# GCDuino5v_v2.net
KiCad netlist of a schematic drawn in EAGLE
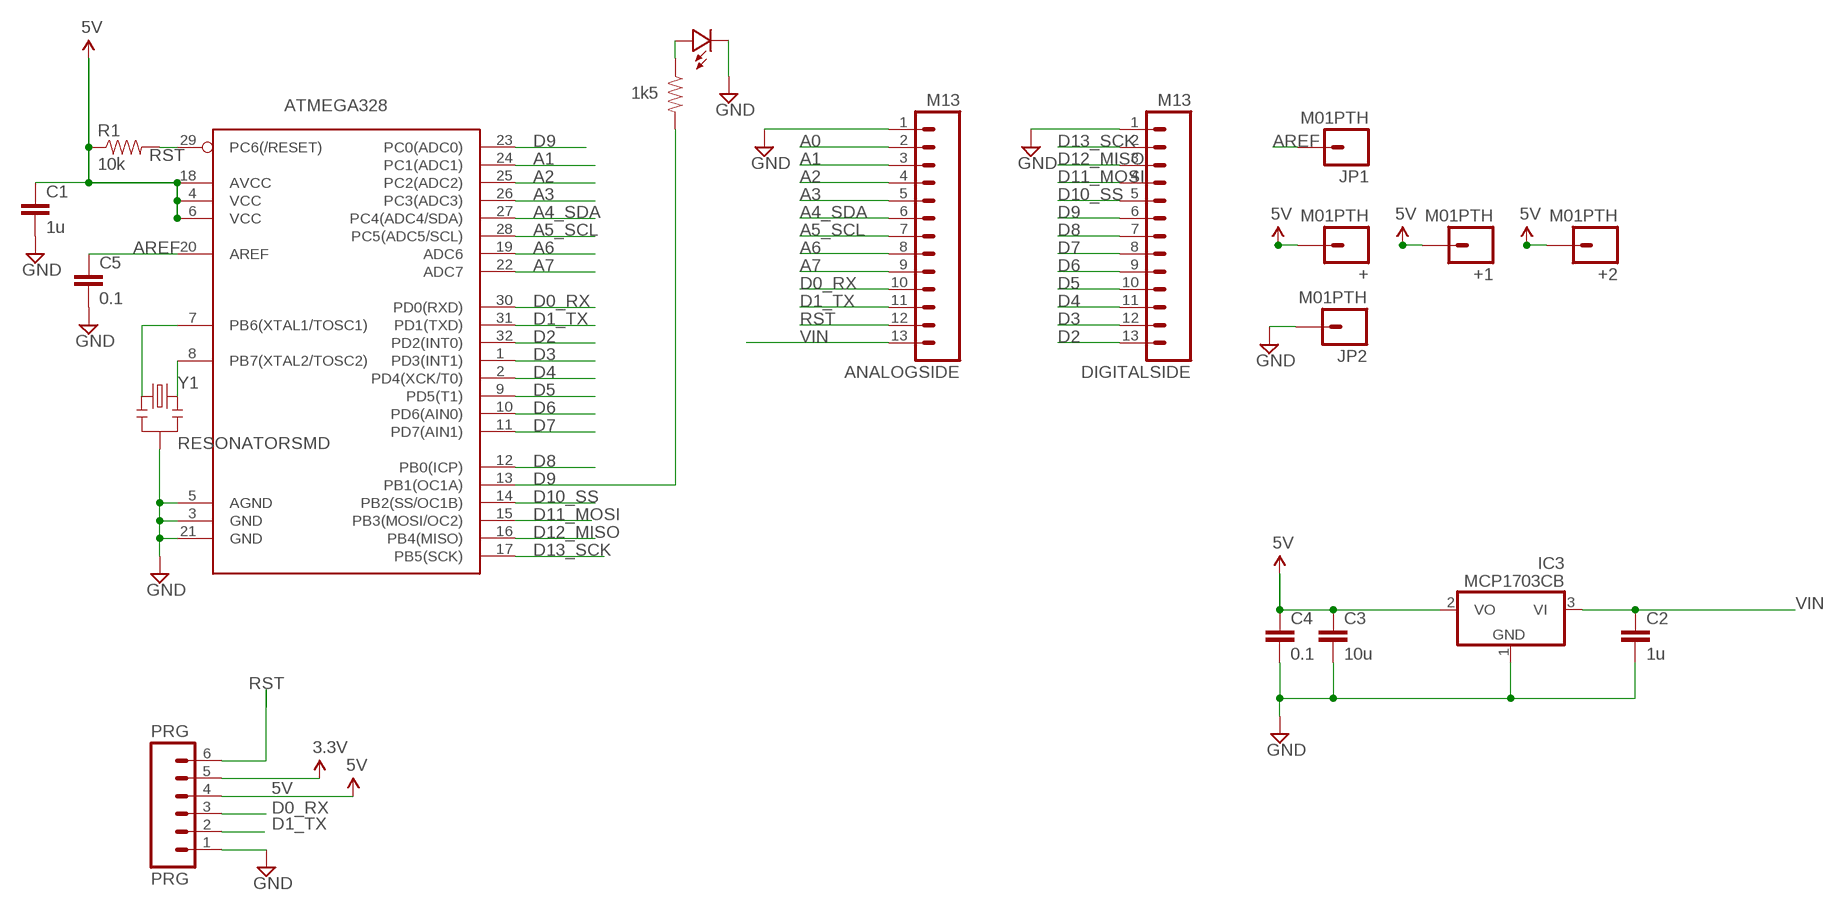
[diagram p0: schematic, sheet 1]

(export (version "E")
  (design (tool "Eeschema 10.0.6"))
  (components
    (comp (ref "+")
      (value "M01PTH")
      (footprint "eagle-import:1X01")
      (libsource (lib "eagle-import") (part "M01PTH"))
    )
    (comp (ref "+1")
      (value "M01PTH")
      (footprint "eagle-import:1X01")
      (libsource (lib "eagle-import") (part "M01PTH"))
    )
    (comp (ref "+2")
      (value "M01PTH")
      (footprint "eagle-import:1X01")
      (libsource (lib "eagle-import") (part "M01PTH"))
    )
    (comp (ref "ANALOGSIDE")
      (value "M13")
      (footprint "eagle-import:1X13")
      (libsource (lib "eagle-import") (part "M13"))
    )
    (comp (ref "ATMEGA328")
      (value "ATMega-328")
      (footprint "eagle-import:TQFP32-08")
      (libsource (lib "eagle-import") (part "ATMEGA168/328TQFP32"))
    )
    (comp (ref "C1")
      (value "1u")
      (footprint "eagle-import:0805")
      (libsource (lib "eagle-import") (part "CAP0805"))
    )
    (comp (ref "C2")
      (value "1u")
      (footprint "eagle-import:0805")
      (libsource (lib "eagle-import") (part "CAP0805"))
    )
    (comp (ref "C3")
      (value "10u")
      (footprint "eagle-import:0805-CAP")
      (libsource (lib "eagle-import") (part "CAP0805-CAP"))
    )
    (comp (ref "C4")
      (value "0.1")
      (footprint "eagle-import:0805")
      (libsource (lib "eagle-import") (part "CAP0805"))
    )
    (comp (ref "C5")
      (value "0.1")
      (footprint "eagle-import:0805")
      (libsource (lib "eagle-import") (part "CAP0805"))
    )
    (comp (ref "DIGITALSIDE")
      (value "M13")
      (footprint "eagle-import:1X13")
      (libsource (lib "eagle-import") (part "M13"))
    )
    (comp (ref "IC3")
      (value "MCP1703CB")
      (footprint "eagle-import:SOT23")
      (libsource (lib "eagle-import") (part "MCP1703CB"))
    )
    (comp (ref "JP1")
      (value "M01PTH")
      (footprint "eagle-import:1X01")
      (libsource (lib "eagle-import") (part "M01PTH"))
    )
    (comp (ref "JP2")
      (value "M01PTH")
      (footprint "eagle-import:1X01")
      (libsource (lib "eagle-import") (part "M01PTH"))
    )
    (comp (ref "PRG")
      (value "PRG")
      (footprint "eagle-import:1X06")
      (libsource (lib "eagle-import") (part "M06SIP"))
    )
    (comp (ref "R1")
      (value "10k")
      (footprint "eagle-import:0805")
      (libsource (lib "eagle-import") (part "RESISTOR0805"))
    )
    (comp (ref "R2")
      (value "1k5")
      (footprint "eagle-import:0805")
      (libsource (lib "eagle-import") (part "RESISTOR0805"))
    )
    (comp (ref "U$2")
      (value "LED0805")
      (footprint "eagle-import:0805-LED")
      (libsource (lib "eagle-import") (part "LED0805"))
    )
    (comp (ref "Y1")
      (value "RESONATORSMD")
      (footprint "eagle-import:RESONATOR-SMD")
      (libsource (lib "eagle-import") (part "RESONATORSMD"))
    )
  )
  (nets
    (net (code "1") (name "/A0") (class "Default")
      (node (ref "ANALOGSIDE") (pin "2") (pinfunction "2_2") (pintype "passive"))
      (node (ref "ATMEGA328") (pin "23") (pinfunction "PC0(ADC0)_23") (pintype "bidirectional"))
    )
    (net (code "2") (name "/A1") (class "Default")
      (node (ref "ANALOGSIDE") (pin "3") (pinfunction "3_3") (pintype "passive"))
      (node (ref "ATMEGA328") (pin "24") (pinfunction "PC1(ADC1)_24") (pintype "bidirectional"))
    )
    (net (code "3") (name "/A2") (class "Default")
      (node (ref "ANALOGSIDE") (pin "4") (pinfunction "4_4") (pintype "passive"))
      (node (ref "ATMEGA328") (pin "25") (pinfunction "PC2(ADC2)_25") (pintype "bidirectional"))
    )
    (net (code "4") (name "/A3") (class "Default")
      (node (ref "ANALOGSIDE") (pin "5") (pinfunction "5_5") (pintype "passive"))
      (node (ref "ATMEGA328") (pin "26") (pinfunction "PC3(ADC3)_26") (pintype "bidirectional"))
    )
    (net (code "5") (name "/A4_SDA") (class "Default")
      (node (ref "ANALOGSIDE") (pin "6") (pinfunction "6_6") (pintype "passive"))
      (node (ref "ATMEGA328") (pin "27") (pinfunction "PC4(ADC4/SDA)_27") (pintype "bidirectional"))
    )
    (net (code "6") (name "/A5_SCL") (class "Default")
      (node (ref "ANALOGSIDE") (pin "7") (pinfunction "7_7") (pintype "passive"))
      (node (ref "ATMEGA328") (pin "28") (pinfunction "PC5(ADC5/SCL)_28") (pintype "bidirectional"))
    )
    (net (code "7") (name "/A6") (class "Default")
      (node (ref "ANALOGSIDE") (pin "8") (pinfunction "8_8") (pintype "passive"))
      (node (ref "ATMEGA328") (pin "19") (pinfunction "ADC6_19") (pintype "bidirectional"))
    )
    (net (code "8") (name "/A7") (class "Default")
      (node (ref "ANALOGSIDE") (pin "9") (pinfunction "9_9") (pintype "passive"))
      (node (ref "ATMEGA328") (pin "22") (pinfunction "ADC7_22") (pintype "bidirectional"))
    )
    (net (code "9") (name "/AREF") (class "Default")
      (node (ref "ATMEGA328") (pin "20") (pinfunction "AREF_20") (pintype "bidirectional"))
      (node (ref "C5") (pin "1") (pinfunction "1_1") (pintype "passive"))
      (node (ref "JP1") (pin "1") (pinfunction "1_1") (pintype "passive"))
    )
    (net (code "10") (name "/D0_RX") (class "Default")
      (node (ref "ANALOGSIDE") (pin "10") (pinfunction "10_10") (pintype "passive"))
      (node (ref "ATMEGA328") (pin "30") (pinfunction "PD0(RXD)_30") (pintype "bidirectional"))
      (node (ref "PRG") (pin "3") (pinfunction "3_3") (pintype "passive"))
    )
    (net (code "11") (name "/D1_TX") (class "Default")
      (node (ref "ANALOGSIDE") (pin "11") (pinfunction "11_11") (pintype "passive"))
      (node (ref "ATMEGA328") (pin "31") (pinfunction "PD1(TXD)_31") (pintype "bidirectional"))
      (node (ref "PRG") (pin "2") (pinfunction "2_2") (pintype "passive"))
    )
    (net (code "12") (name "/D2") (class "Default")
      (node (ref "ATMEGA328") (pin "32") (pinfunction "PD2(INT0)_32") (pintype "bidirectional"))
      (node (ref "DIGITALSIDE") (pin "13") (pinfunction "13_13") (pintype "passive"))
    )
    (net (code "13") (name "/D3") (class "Default")
      (node (ref "ATMEGA328") (pin "1") (pinfunction "PD3(INT1)_1") (pintype "bidirectional"))
      (node (ref "DIGITALSIDE") (pin "12") (pinfunction "12_12") (pintype "passive"))
    )
    (net (code "14") (name "/D4") (class "Default")
      (node (ref "ATMEGA328") (pin "2") (pinfunction "PD4(XCK/T0)_2") (pintype "bidirectional"))
      (node (ref "DIGITALSIDE") (pin "11") (pinfunction "11_11") (pintype "passive"))
    )
    (net (code "15") (name "/D5") (class "Default")
      (node (ref "ATMEGA328") (pin "9") (pinfunction "PD5(T1)_9") (pintype "bidirectional"))
      (node (ref "DIGITALSIDE") (pin "10") (pinfunction "10_10") (pintype "passive"))
    )
    (net (code "16") (name "/D6") (class "Default")
      (node (ref "ATMEGA328") (pin "10") (pinfunction "PD6(AIN0)_10") (pintype "bidirectional"))
      (node (ref "DIGITALSIDE") (pin "9") (pinfunction "9_9") (pintype "passive"))
    )
    (net (code "17") (name "/D7") (class "Default")
      (node (ref "ATMEGA328") (pin "11") (pinfunction "PD7(AIN1)_11") (pintype "bidirectional"))
      (node (ref "DIGITALSIDE") (pin "8") (pinfunction "8_8") (pintype "passive"))
    )
    (net (code "18") (name "/D8") (class "Default")
      (node (ref "ATMEGA328") (pin "12") (pinfunction "PB0(ICP)_12") (pintype "bidirectional"))
      (node (ref "DIGITALSIDE") (pin "7") (pinfunction "7_7") (pintype "passive"))
    )
    (net (code "19") (name "/D9") (class "Default")
      (node (ref "ATMEGA328") (pin "13") (pinfunction "PB1(OC1A)_13") (pintype "bidirectional"))
      (node (ref "DIGITALSIDE") (pin "6") (pinfunction "6_6") (pintype "passive"))
      (node (ref "R2") (pin "2") (pinfunction "2_2") (pintype "passive"))
    )
    (net (code "20") (name "/D10_SS") (class "Default")
      (node (ref "ATMEGA328") (pin "14") (pinfunction "PB2(SS/OC1B)_14") (pintype "bidirectional"))
      (node (ref "DIGITALSIDE") (pin "5") (pinfunction "5_5") (pintype "passive"))
    )
    (net (code "21") (name "/D11_MOSI") (class "Default")
      (node (ref "ATMEGA328") (pin "15") (pinfunction "PB3(MOSI/OC2)_15") (pintype "bidirectional"))
      (node (ref "DIGITALSIDE") (pin "4") (pinfunction "4_4") (pintype "passive"))
    )
    (net (code "22") (name "/D12_MISO") (class "Default")
      (node (ref "ATMEGA328") (pin "16") (pinfunction "PB4(MISO)_16") (pintype "bidirectional"))
      (node (ref "DIGITALSIDE") (pin "3") (pinfunction "3_3") (pintype "passive"))
    )
    (net (code "23") (name "/D13_SCK") (class "Default")
      (node (ref "ATMEGA328") (pin "17") (pinfunction "PB5(SCK)_17") (pintype "bidirectional"))
      (node (ref "DIGITALSIDE") (pin "2") (pinfunction "2_2") (pintype "passive"))
    )
    (net (code "24") (name "/RST") (class "Default")
      (node (ref "ANALOGSIDE") (pin "12") (pinfunction "12_12") (pintype "passive"))
      (node (ref "ATMEGA328") (pin "29") (pinfunction "PC6(/RESET)_29") (pintype "bidirectional"))
      (node (ref "PRG") (pin "6") (pinfunction "6_6") (pintype "passive"))
      (node (ref "R1") (pin "2") (pinfunction "2_2") (pintype "passive"))
    )
    (net (code "25") (name "/VIN") (class "Default")
      (node (ref "ANALOGSIDE") (pin "13") (pinfunction "13_13") (pintype "passive"))
      (node (ref "C2") (pin "1") (pinfunction "1_1") (pintype "passive"))
      (node (ref "IC3") (pin "3") (pinfunction "VI_3") (pintype "input"))
    )
    (net (code "26") (name "3.3V") (class "Default")
      (node (ref "PRG") (pin "5") (pinfunction "5_5") (pintype "passive"))
    )
    (net (code "27") (name "5V") (class "Default")
      (node (ref "+") (pin "1") (pinfunction "1_1") (pintype "passive"))
      (node (ref "+1") (pin "1") (pinfunction "1_1") (pintype "passive"))
      (node (ref "+2") (pin "1") (pinfunction "1_1") (pintype "passive"))
      (node (ref "ATMEGA328") (pin "18") (pinfunction "AVCC_18") (pintype "bidirectional"))
      (node (ref "ATMEGA328") (pin "4") (pinfunction "VCC_4") (pintype "bidirectional"))
      (node (ref "ATMEGA328") (pin "6") (pinfunction "VCC_6") (pintype "bidirectional"))
      (node (ref "C1") (pin "1") (pinfunction "1_1") (pintype "passive"))
      (node (ref "C3") (pin "1") (pinfunction "1_1") (pintype "passive"))
      (node (ref "C4") (pin "1") (pinfunction "1_1") (pintype "passive"))
      (node (ref "IC3") (pin "2") (pinfunction "VO_2") (pintype "passive"))
      (node (ref "PRG") (pin "4") (pinfunction "4_4") (pintype "passive"))
      (node (ref "R1") (pin "1") (pinfunction "1_1") (pintype "passive"))
    )
    (net (code "28") (name "GND") (class "Default")
      (node (ref "ANALOGSIDE") (pin "1") (pinfunction "1_1") (pintype "passive"))
      (node (ref "ATMEGA328") (pin "21") (pinfunction "GND_21") (pintype "bidirectional"))
      (node (ref "ATMEGA328") (pin "3") (pinfunction "GND_3") (pintype "bidirectional"))
      (node (ref "ATMEGA328") (pin "5") (pinfunction "AGND_5") (pintype "bidirectional"))
      (node (ref "C1") (pin "2") (pinfunction "2_2") (pintype "passive"))
      (node (ref "C2") (pin "2") (pinfunction "2_2") (pintype "passive"))
      (node (ref "C3") (pin "2") (pinfunction "2_2") (pintype "passive"))
      (node (ref "C4") (pin "2") (pinfunction "2_2") (pintype "passive"))
      (node (ref "C5") (pin "2") (pinfunction "2_2") (pintype "passive"))
      (node (ref "DIGITALSIDE") (pin "1") (pinfunction "1_1") (pintype "passive"))
      (node (ref "IC3") (pin "1") (pinfunction "GND_1") (pintype "passive"))
      (node (ref "JP2") (pin "1") (pinfunction "1_1") (pintype "passive"))
      (node (ref "PRG") (pin "1") (pinfunction "1_1") (pintype "passive"))
      (node (ref "U$2") (pin "MINUS") (pinfunction "MINUS_MINUS") (pintype "passive"))
      (node (ref "Y1") (pin "2") (pinfunction "2_2") (pintype "passive"))
    )
    (net (code "29") (name "Net-(ATMEGA328-PB6(XTAL1{slash}TOSC1))") (class "Default")
      (node (ref "ATMEGA328") (pin "7") (pinfunction "PB6(XTAL1/TOSC1)_7") (pintype "bidirectional"))
      (node (ref "Y1") (pin "1") (pinfunction "1_1") (pintype "passive"))
    )
    (net (code "30") (name "Net-(ATMEGA328-PB7(XTAL2{slash}TOSC2))") (class "Default")
      (node (ref "ATMEGA328") (pin "8") (pinfunction "PB7(XTAL2/TOSC2)_8") (pintype "bidirectional"))
      (node (ref "Y1") (pin "3") (pinfunction "3_3") (pintype "passive"))
    )
    (net (code "31") (name "Net-(R2-Pad1)") (class "Default")
      (node (ref "R2") (pin "1") (pinfunction "1_1") (pintype "passive"))
      (node (ref "U$2") (pin "PLUS") (pinfunction "PLUS_PLUS") (pintype "passive"))
    )
  )
)
